# LoRaWANnode.net
KiCad netlist of a schematic drawn in EAGLE
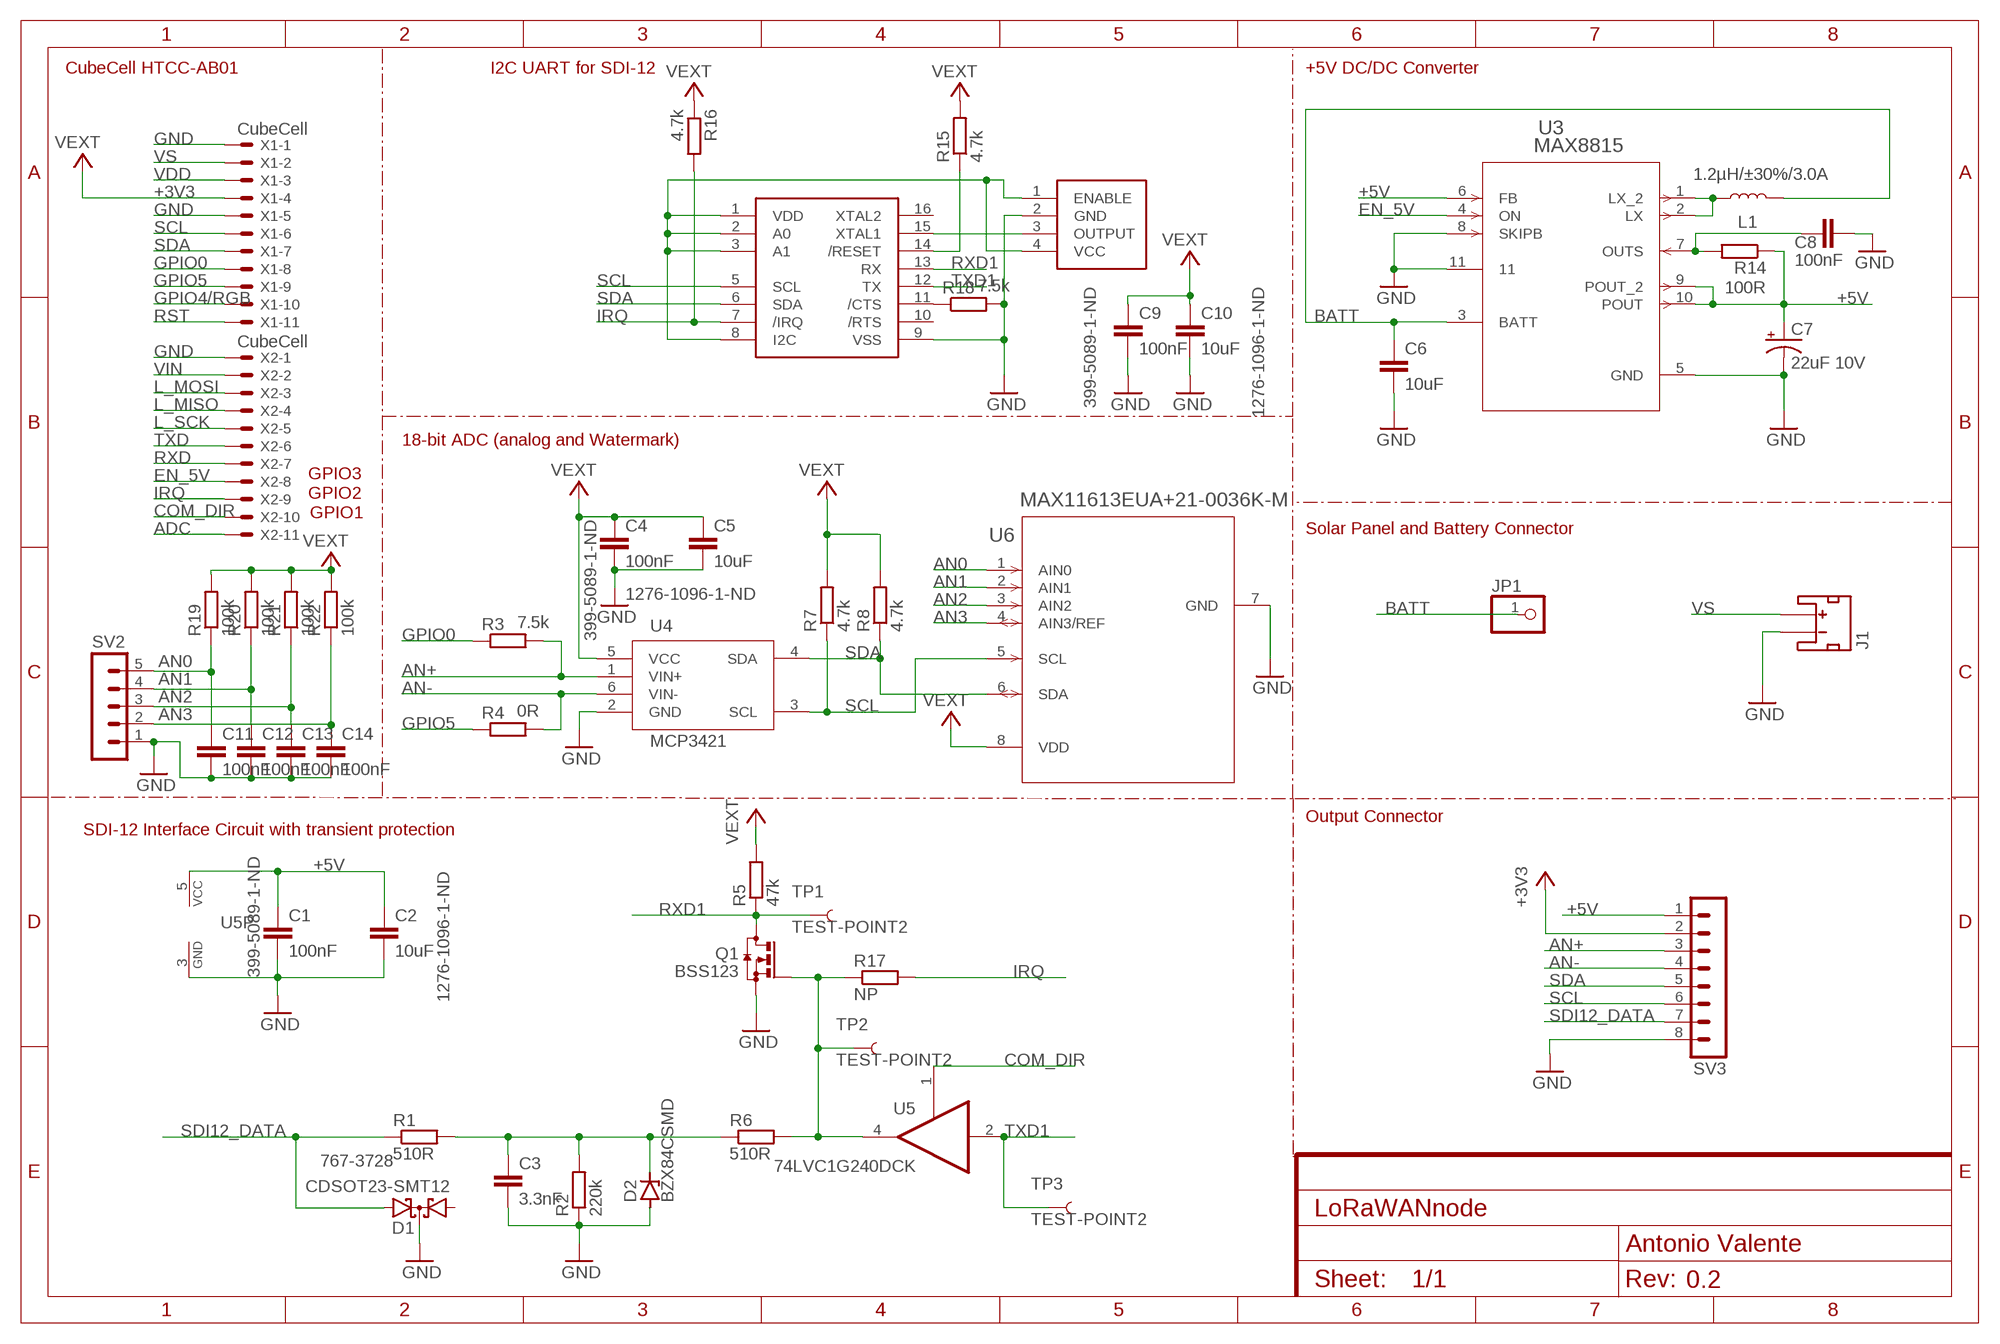
[diagram p0: schematic, sheet 1]

(export (version "E")
  (design (tool "Eeschema 10.0.6"))
  (components
    (comp (ref "C1")
      (value "100nF")
      (footprint "eagle-import:SCHMALZHAUS_0603-CAP")
      (fields
        (field (name "MF") "AVX")
        (field (name "MPN") "06033C104KAT4A")
        (field (name "OC_DIGIKEY") "399-5089-1-ND")
      )
      (libsource (lib "eagle-import") (part "SCHMALZHAUS_CAP0603-CAP"))
    )
    (comp (ref "C2")
      (value "10uF")
      (footprint "eagle-import:SCHMALZHAUS_0603-CAP")
      (fields
        (field (name "MF") "AVX")
        (field (name "MPN") "0805ZC106KAT2A")
        (field (name "OC_DIGIKEY") "1276-1096-1-ND")
      )
      (libsource (lib "eagle-import") (part "SCHMALZHAUS_CAP0603-CAP"))
    )
    (comp (ref "C3")
      (value "3.3nF")
      (footprint "eagle-import:C0603K")
      (libsource (lib "eagle-import") (part "C-EUC0603K"))
    )
    (comp (ref "C4")
      (value "100nF")
      (footprint "eagle-import:SCHMALZHAUS_0603-CAP")
      (fields
        (field (name "MF") "AVX")
        (field (name "MPN") "06033C104KAT4A")
        (field (name "OC_DIGIKEY") "399-5089-1-ND")
      )
      (libsource (lib "eagle-import") (part "SCHMALZHAUS_CAP0603-CAP"))
    )
    (comp (ref "C5")
      (value "10uF")
      (footprint "eagle-import:SCHMALZHAUS_0603-CAP")
      (fields
        (field (name "MF") "AVX")
        (field (name "MPN") "0805ZC106KAT2A")
        (field (name "OC_DIGIKEY") "1276-1096-1-ND")
      )
      (libsource (lib "eagle-import") (part "SCHMALZHAUS_CAP0603-CAP"))
    )
    (comp (ref "C6")
      (value "10uF")
      (footprint "eagle-import:0805")
      (libsource (lib "eagle-import") (part "10UF-0805-10V-10%"))
    )
    (comp (ref "C7")
      (value "22uF 10V")
      (footprint "eagle-import:EIA3216")
      (libsource (lib "eagle-import") (part "10UF-POLAR-EIA3216-16V-10%(TANT)"))
    )
    (comp (ref "C8")
      (value "100nF")
      (footprint "eagle-import:C0603K")
      (libsource (lib "eagle-import") (part "C-EUC0603K"))
    )
    (comp (ref "C9")
      (value "100nF")
      (footprint "eagle-import:SCHMALZHAUS_0603-CAP")
      (fields
        (field (name "MF") "AVX")
        (field (name "MPN") "06033C104KAT4A")
        (field (name "OC_DIGIKEY") "399-5089-1-ND")
      )
      (libsource (lib "eagle-import") (part "SCHMALZHAUS_CAP0603-CAP"))
    )
    (comp (ref "C10")
      (value "10uF")
      (footprint "eagle-import:SCHMALZHAUS_0603-CAP")
      (fields
        (field (name "MF") "AVX")
        (field (name "MPN") "0805ZC106KAT2A")
        (field (name "OC_DIGIKEY") "1276-1096-1-ND")
      )
      (libsource (lib "eagle-import") (part "SCHMALZHAUS_CAP0603-CAP"))
    )
    (comp (ref "C11")
      (value "100nF")
      (footprint "eagle-import:SCHMALZHAUS_0603-CAP")
      (fields
        (field (name "MF") "AVX")
        (field (name "MPN") "06033C104KAT4A")
        (field (name "OC_DIGIKEY") "399-5089-1-ND")
      )
      (libsource (lib "eagle-import") (part "SCHMALZHAUS_CAP0603-CAP"))
    )
    (comp (ref "C12")
      (value "100nF")
      (footprint "eagle-import:SCHMALZHAUS_0603-CAP")
      (fields
        (field (name "MF") "AVX")
        (field (name "MPN") "06033C104KAT4A")
        (field (name "OC_DIGIKEY") "399-5089-1-ND")
      )
      (libsource (lib "eagle-import") (part "SCHMALZHAUS_CAP0603-CAP"))
    )
    (comp (ref "C13")
      (value "100nF")
      (footprint "eagle-import:SCHMALZHAUS_0603-CAP")
      (fields
        (field (name "MF") "AVX")
        (field (name "MPN") "06033C104KAT4A")
        (field (name "OC_DIGIKEY") "399-5089-1-ND")
      )
      (libsource (lib "eagle-import") (part "SCHMALZHAUS_CAP0603-CAP"))
    )
    (comp (ref "C14")
      (value "100nF")
      (footprint "eagle-import:SCHMALZHAUS_0603-CAP")
      (fields
        (field (name "MF") "AVX")
        (field (name "MPN") "06033C104KAT4A")
        (field (name "OC_DIGIKEY") "399-5089-1-ND")
      )
      (libsource (lib "eagle-import") (part "SCHMALZHAUS_CAP0603-CAP"))
    )
    (comp (ref "D1")
      (value "CDSOT23-SMT12")
      (footprint "eagle-import:SOT23")
      (fields (field (name "RS") "767-3728"))
      (libsource (lib "eagle-import") (part "BAS40-05"))
    )
    (comp (ref "D2")
      (value "BZX84CSMD")
      (footprint "eagle-import:TO236")
      (libsource (lib "eagle-import") (part "BZX84CSMD"))
    )
    (comp (ref "J1")
      (value "JST_2MM_MALE")
      (footprint "eagle-import:JST-2-SMD")
      (libsource (lib "eagle-import") (part "JST_2MM_MALE"))
    )
    (comp (ref "JP1")
      (value "PINHD-1X1CB")
      (footprint "eagle-import:1X01-CLEANBIG")
      (libsource (lib "eagle-import") (part "PINHD-1X1CB"))
    )
    (comp (ref "L1")
      (value "1.2µH/±30%/3.0A")
      (footprint "eagle-import:CR54")
      (libsource (lib "eagle-import") (part "INDUCTOR-CR54-3.3UH"))
    )
    (comp (ref "Q1")
      (value "BSS123")
      (footprint "eagle-import:SOT23")
      (libsource (lib "eagle-import") (part "BSS123"))
    )
    (comp (ref "R1")
      (value "510R")
      (footprint "eagle-import:R0603")
      (libsource (lib "eagle-import") (part "resistor_348_R-EU_R0603"))
    )
    (comp (ref "R2")
      (value "220k")
      (footprint "eagle-import:R0603")
      (libsource (lib "eagle-import") (part "resistor_348_R-EU_R0603"))
    )
    (comp (ref "R3")
      (value "7.5k")
      (footprint "eagle-import:R0603")
      (libsource (lib "eagle-import") (part "resistor_348_R-EU_R0603"))
    )
    (comp (ref "R4")
      (value "0R")
      (footprint "eagle-import:R0603")
      (libsource (lib "eagle-import") (part "resistor_348_R-EU_R0603"))
    )
    (comp (ref "R5")
      (value "47k")
      (footprint "eagle-import:R0603")
      (libsource (lib "eagle-import") (part "resistor_348_R-EU_R0603"))
    )
    (comp (ref "R6")
      (value "510R")
      (footprint "eagle-import:R0603")
      (libsource (lib "eagle-import") (part "resistor_348_R-EU_R0603"))
    )
    (comp (ref "R7")
      (value "4.7k")
      (footprint "eagle-import:R0603")
      (libsource (lib "eagle-import") (part "R-EU_R0603"))
    )
    (comp (ref "R8")
      (value "4.7k")
      (footprint "eagle-import:R0603")
      (libsource (lib "eagle-import") (part "R-EU_R0603"))
    )
    (comp (ref "R14")
      (value "100R")
      (footprint "eagle-import:R0603")
      (libsource (lib "eagle-import") (part "resistor_348_R-EU_R0603"))
    )
    (comp (ref "R15")
      (value "4.7k")
      (footprint "eagle-import:R0603")
      (libsource (lib "eagle-import") (part "R-EU_R0603"))
    )
    (comp (ref "R16")
      (value "4.7k")
      (footprint "eagle-import:R0603")
      (libsource (lib "eagle-import") (part "R-EU_R0603"))
    )
    (comp (ref "R17")
      (value "NP")
      (footprint "eagle-import:R0603")
      (libsource (lib "eagle-import") (part "resistor_348_R-EU_R0603"))
    )
    (comp (ref "R18")
      (value "7.5k")
      (footprint "eagle-import:R0603")
      (libsource (lib "eagle-import") (part "resistor_348_R-EU_R0603"))
    )
    (comp (ref "R19")
      (value "100k")
      (footprint "eagle-import:R0603")
      (libsource (lib "eagle-import") (part "R-EU_R0603"))
    )
    (comp (ref "R20")
      (value "100k")
      (footprint "eagle-import:R0603")
      (libsource (lib "eagle-import") (part "R-EU_R0603"))
    )
    (comp (ref "R21")
      (value "100k")
      (footprint "eagle-import:R0603")
      (libsource (lib "eagle-import") (part "R-EU_R0603"))
    )
    (comp (ref "R22")
      (value "100k")
      (footprint "eagle-import:R0603")
      (libsource (lib "eagle-import") (part "R-EU_R0603"))
    )
    (comp (ref "SV2")
      (value "MA05-1")
      (footprint "eagle-import:MA05-1")
      (libsource (lib "eagle-import") (part "MA05-1"))
    )
    (comp (ref "SV3")
      (value "MA08-1")
      (footprint "eagle-import:MA08-1")
      (libsource (lib "eagle-import") (part "MA08-1"))
    )
    (comp (ref "TP1")
      (value "TEST-POINT2")
      (footprint "eagle-import:PAD.02X.02")
      (libsource (lib "eagle-import") (part "TEST-POINT2"))
    )
    (comp (ref "TP2")
      (value "TEST-POINT2")
      (footprint "eagle-import:PAD.02X.02")
      (libsource (lib "eagle-import") (part "TEST-POINT2"))
    )
    (comp (ref "TP3")
      (value "TEST-POINT2")
      (footprint "eagle-import:PAD.02X.02")
      (libsource (lib "eagle-import") (part "TEST-POINT2"))
    )
    (comp (ref "U1")
      (value "RICKK2_SC16IS740")
      (footprint "eagle-import:RICKK2_SC16IS740")
      (libsource (lib "eagle-import") (part "RICKK2_SC16IS740"))
    )
    (comp (ref "U2")
      (value "RICKK2_OSC-KC3225K")
      (footprint "eagle-import:RICKK2_OSC-KC3225K")
      (libsource (lib "eagle-import") (part "RICKK2_OSC-KC3225K"))
    )
    (comp (ref "U3")
      (value "MAX8815")
      (footprint "eagle-import:21-0137I_T1033-1-M")
      (fields (field (name "MANUFACTURER_PART_NUMBER") "max8815aetb+"))
      (libsource (lib "eagle-import") (part "MAX8815AETB+21-0137I_T1033-1-M"))
    )
    (comp (ref "U4")
      (value "MCP3421")
      (footprint "eagle-import:SOT23-6")
      (fields (field (name "MF") "MICROCHIP") (field (name "MPN") "MCP3421A0T-E/CH"))
      (libsource (lib "eagle-import") (part "MCP3421"))
    )
    (comp (ref "U5")
      (value "74LVC1G240DCK")
      (footprint "eagle-import:SC70-5")
      (libsource (lib "eagle-import") (part "741G126DCKLVC"))
    )
    (comp (ref "U6")
      (value "MAX11613EUA+21-0036K-M")
      (footprint "eagle-import:21-0036K-M")
      (fields (field (name "MANUFACTURER_PART_NUMBER") "max11613eua+"))
      (libsource (lib "eagle-import") (part "MAX11613EUA+21-0036K-M"))
    )
    (comp (ref "X1")
      (value "CubeCell")
      (footprint "eagle-import:22-23-2111")
      (fields (field (name "MF") "MOLEX") (field (name "MPN") "22-23-2111"))
      (libsource (lib "eagle-import") (part "22-23-2111"))
    )
    (comp (ref "X2")
      (value "CubeCell")
      (footprint "eagle-import:22-23-2111")
      (fields (field (name "MF") "MOLEX") (field (name "MPN") "22-23-2111"))
      (libsource (lib "eagle-import") (part "22-23-2111"))
    )
  )
  (nets
    (net (code "1") (name "+3V3") (class "Default")
      (node (ref "C10") (pin "1") (pinfunction "1_1") (pintype "passive"))
      (node (ref "C4") (pin "1") (pinfunction "1_1") (pintype "passive"))
      (node (ref "C5") (pin "1") (pinfunction "1_1") (pintype "passive"))
      (node (ref "C9") (pin "1") (pinfunction "1_1") (pintype "passive"))
      (node (ref "R15") (pin "2") (pinfunction "2_2") (pintype "passive"))
      (node (ref "R16") (pin "1") (pinfunction "1_1") (pintype "passive"))
      (node (ref "R19") (pin "2") (pinfunction "2_2") (pintype "passive"))
      (node (ref "R20") (pin "2") (pinfunction "2_2") (pintype "passive"))
      (node (ref "R21") (pin "2") (pinfunction "2_2") (pintype "passive"))
      (node (ref "R22") (pin "2") (pinfunction "2_2") (pintype "passive"))
      (node (ref "R5") (pin "2") (pinfunction "2_2") (pintype "passive"))
      (node (ref "R7") (pin "2") (pinfunction "2_2") (pintype "passive"))
      (node (ref "R8") (pin "2") (pinfunction "2_2") (pintype "passive"))
      (node (ref "SV3") (pin "2") (pinfunction "2_2") (pintype "passive"))
      (node (ref "U1") (pin "1") (pinfunction "VDD_1") (pintype "power_in"))
      (node (ref "U1") (pin "2") (pinfunction "A0_2") (pintype "input"))
      (node (ref "U1") (pin "3") (pinfunction "A1_3") (pintype "input"))
      (node (ref "U1") (pin "8") (pinfunction "I2C_8") (pintype "input"))
      (node (ref "U2") (pin "1") (pinfunction "ENABLE_1") (pintype "input"))
      (node (ref "U2") (pin "4") (pinfunction "VCC_4") (pintype "power_in"))
      (node (ref "U4") (pin "5") (pinfunction "VCC_5") (pintype "passive"))
      (node (ref "U6") (pin "8") (pinfunction "VDD_8") (pintype "power_in"))
      (node (ref "X1") (pin "4") (pinfunction "S_4") (pintype "passive"))
    )
    (net (code "2") (name "/+5V") (class "Default")
      (node (ref "C1") (pin "1") (pinfunction "1_1") (pintype "passive"))
      (node (ref "C2") (pin "1") (pinfunction "1_1") (pintype "passive"))
      (node (ref "C7") (pin "+") (pinfunction "+_+") (pintype "passive"))
      (node (ref "R14") (pin "1") (pinfunction "1_1") (pintype "passive"))
      (node (ref "SV3") (pin "1") (pinfunction "1_1") (pintype "passive"))
      (node (ref "U3") (pin "10") (pinfunction "POUT_10") (pintype "output"))
      (node (ref "U3") (pin "6") (pinfunction "FB_6") (pintype "input"))
      (node (ref "U3") (pin "9") (pinfunction "POUT_2_9") (pintype "output"))
      (node (ref "U5") (pin "5") (pinfunction "VCC_5") (pintype "power_in"))
    )
    (net (code "3") (name "/ADC") (class "Default")
      (node (ref "X2") (pin "11") (pinfunction "S_11") (pintype "passive"))
    )
    (net (code "4") (name "/AN+") (class "Default")
      (node (ref "R3") (pin "2") (pinfunction "2_2") (pintype "passive"))
      (node (ref "SV3") (pin "3") (pinfunction "3_3") (pintype "passive"))
      (node (ref "U4") (pin "1") (pinfunction "VIN+_1") (pintype "passive"))
    )
    (net (code "5") (name "/AN-") (class "Default")
      (node (ref "R4") (pin "2") (pinfunction "2_2") (pintype "passive"))
      (node (ref "SV3") (pin "4") (pinfunction "4_4") (pintype "passive"))
      (node (ref "U4") (pin "6") (pinfunction "VIN-_6") (pintype "passive"))
    )
    (net (code "6") (name "/AN0") (class "Default")
      (node (ref "C11") (pin "1") (pinfunction "1_1") (pintype "passive"))
      (node (ref "R19") (pin "1") (pinfunction "1_1") (pintype "passive"))
      (node (ref "SV2") (pin "5") (pinfunction "5_5") (pintype "passive"))
      (node (ref "U6") (pin "1") (pinfunction "AIN0_1") (pintype "input"))
    )
    (net (code "7") (name "/AN1") (class "Default")
      (node (ref "C12") (pin "1") (pinfunction "1_1") (pintype "passive"))
      (node (ref "R20") (pin "1") (pinfunction "1_1") (pintype "passive"))
      (node (ref "SV2") (pin "4") (pinfunction "4_4") (pintype "passive"))
      (node (ref "U6") (pin "2") (pinfunction "AIN1_2") (pintype "input"))
    )
    (net (code "8") (name "/AN2") (class "Default")
      (node (ref "C13") (pin "1") (pinfunction "1_1") (pintype "passive"))
      (node (ref "R21") (pin "1") (pinfunction "1_1") (pintype "passive"))
      (node (ref "SV2") (pin "3") (pinfunction "3_3") (pintype "passive"))
      (node (ref "U6") (pin "3") (pinfunction "AIN2_3") (pintype "input"))
    )
    (net (code "9") (name "/AN3") (class "Default")
      (node (ref "C14") (pin "1") (pinfunction "1_1") (pintype "passive"))
      (node (ref "R22") (pin "1") (pinfunction "1_1") (pintype "passive"))
      (node (ref "SV2") (pin "2") (pinfunction "2_2") (pintype "passive"))
      (node (ref "U6") (pin "4") (pinfunction "AIN3/REF_4") (pintype "bidirectional"))
    )
    (net (code "10") (name "/BATT") (class "Default")
      (node (ref "C6") (pin "1") (pinfunction "1_1") (pintype "passive"))
      (node (ref "JP1") (pin "1") (pinfunction "1_1") (pintype "passive"))
      (node (ref "L1") (pin "P$2") (pinfunction "2_P$2") (pintype "passive"))
      (node (ref "U3") (pin "3") (pinfunction "BATT_3") (pintype "power_in"))
    )
    (net (code "11") (name "/COM_DIR") (class "Default")
      (node (ref "U5") (pin "1") (pinfunction "OE_1") (pintype "input"))
      (node (ref "X2") (pin "10") (pinfunction "S_10") (pintype "passive"))
    )
    (net (code "12") (name "/EN_5V") (class "Default")
      (node (ref "U3") (pin "4") (pinfunction "ON_4") (pintype "input"))
      (node (ref "X2") (pin "8") (pinfunction "S_8") (pintype "passive"))
    )
    (net (code "13") (name "/GPIO0") (class "Default")
      (node (ref "R3") (pin "1") (pinfunction "1_1") (pintype "passive"))
      (node (ref "X1") (pin "8") (pinfunction "S_8") (pintype "passive"))
    )
    (net (code "14") (name "/GPIO4{slash}RGB") (class "Default")
      (node (ref "X1") (pin "10") (pinfunction "S_10") (pintype "passive"))
    )
    (net (code "15") (name "/GPIO5") (class "Default")
      (node (ref "R4") (pin "1") (pinfunction "1_1") (pintype "passive"))
      (node (ref "X1") (pin "9") (pinfunction "S_9") (pintype "passive"))
    )
    (net (code "16") (name "/IRQ") (class "Default")
      (node (ref "R16") (pin "2") (pinfunction "2_2") (pintype "passive"))
      (node (ref "R17") (pin "2") (pinfunction "2_2") (pintype "passive"))
      (node (ref "U1") (pin "7") (pinfunction "/IRQ_7") (pintype "output"))
      (node (ref "X2") (pin "9") (pinfunction "S_9") (pintype "passive"))
    )
    (net (code "17") (name "/L_MISO") (class "Default")
      (node (ref "X2") (pin "4") (pinfunction "S_4") (pintype "passive"))
    )
    (net (code "18") (name "/L_MOSI") (class "Default")
      (node (ref "X2") (pin "3") (pinfunction "S_3") (pintype "passive"))
    )
    (net (code "19") (name "/L_SCK") (class "Default")
      (node (ref "X2") (pin "5") (pinfunction "S_5") (pintype "passive"))
    )
    (net (code "20") (name "/RST") (class "Default")
      (node (ref "X1") (pin "11") (pinfunction "S_11") (pintype "passive"))
    )
    (net (code "21") (name "/RXD") (class "Default")
      (node (ref "X2") (pin "7") (pinfunction "S_7") (pintype "passive"))
    )
    (net (code "22") (name "/RXD1") (class "Default")
      (node (ref "Q1") (pin "3") (pinfunction "D_3") (pintype "passive"))
      (node (ref "R5") (pin "1") (pinfunction "1_1") (pintype "passive"))
      (node (ref "TP1") (pin "P$1") (pinfunction "1_P$1") (pintype "bidirectional"))
      (node (ref "U1") (pin "13") (pinfunction "RX_13") (pintype "input"))
    )
    (net (code "23") (name "/SCL") (class "Default")
      (node (ref "R7") (pin "1") (pinfunction "1_1") (pintype "passive"))
      (node (ref "SV3") (pin "6") (pinfunction "6_6") (pintype "passive"))
      (node (ref "U1") (pin "5") (pinfunction "SCL_5") (pintype "bidirectional"))
      (node (ref "U4") (pin "3") (pinfunction "SCL_3") (pintype "passive"))
      (node (ref "U6") (pin "5") (pinfunction "SCL_5") (pintype "input"))
      (node (ref "X1") (pin "6") (pinfunction "S_6") (pintype "passive"))
    )
    (net (code "24") (name "/SDA") (class "Default")
      (node (ref "R8") (pin "1") (pinfunction "1_1") (pintype "passive"))
      (node (ref "SV3") (pin "5") (pinfunction "5_5") (pintype "passive"))
      (node (ref "U1") (pin "6") (pinfunction "SDA_6") (pintype "bidirectional"))
      (node (ref "U4") (pin "4") (pinfunction "SDA_4") (pintype "passive"))
      (node (ref "U6") (pin "6") (pinfunction "SDA_6") (pintype "bidirectional"))
      (node (ref "X1") (pin "7") (pinfunction "S_7") (pintype "passive"))
    )
    (net (code "25") (name "/SDI12_DATA") (class "Default")
      (node (ref "D1") (pin "2") (pinfunction "A2_2") (pintype "passive"))
      (node (ref "R1") (pin "1") (pinfunction "1_1") (pintype "passive"))
      (node (ref "SV3") (pin "7") (pinfunction "7_7") (pintype "passive"))
    )
    (net (code "26") (name "/TXD") (class "Default")
      (node (ref "X2") (pin "6") (pinfunction "S_6") (pintype "passive"))
    )
    (net (code "27") (name "/TXD1") (class "Default")
      (node (ref "TP3") (pin "P$1") (pinfunction "1_P$1") (pintype "bidirectional"))
      (node (ref "U1") (pin "12") (pinfunction "TX_12") (pintype "output"))
      (node (ref "U5") (pin "2") (pinfunction "I_2") (pintype "input"))
    )
    (net (code "28") (name "/VDD") (class "Default")
      (node (ref "X1") (pin "3") (pinfunction "S_3") (pintype "passive"))
    )
    (net (code "29") (name "/VIN") (class "Default")
      (node (ref "X2") (pin "2") (pinfunction "S_2") (pintype "passive"))
    )
    (net (code "30") (name "/VS") (class "Default")
      (node (ref "J1") (pin "2") (pinfunction "+_2") (pintype "bidirectional"))
      (node (ref "X1") (pin "2") (pinfunction "S_2") (pintype "passive"))
    )
    (net (code "31") (name "GND") (class "Default")
      (node (ref "C1") (pin "2") (pinfunction "2_2") (pintype "passive"))
      (node (ref "C10") (pin "2") (pinfunction "2_2") (pintype "passive"))
      (node (ref "C11") (pin "2") (pinfunction "2_2") (pintype "passive"))
      (node (ref "C12") (pin "2") (pinfunction "2_2") (pintype "passive"))
      (node (ref "C13") (pin "2") (pinfunction "2_2") (pintype "passive"))
      (node (ref "C14") (pin "2") (pinfunction "2_2") (pintype "passive"))
      (node (ref "C2") (pin "2") (pinfunction "2_2") (pintype "passive"))
      (node (ref "C3") (pin "2") (pinfunction "2_2") (pintype "passive"))
      (node (ref "C4") (pin "2") (pinfunction "2_2") (pintype "passive"))
      (node (ref "C5") (pin "2") (pinfunction "2_2") (pintype "passive"))
      (node (ref "C6") (pin "2") (pinfunction "2_2") (pintype "passive"))
      (node (ref "C7") (pin "-") (pinfunction "-_-") (pintype "passive"))
      (node (ref "C8") (pin "2") (pinfunction "2_2") (pintype "passive"))
      (node (ref "C9") (pin "2") (pinfunction "2_2") (pintype "passive"))
      (node (ref "D1") (pin "3") (pinfunction "C_3") (pintype "passive"))
      (node (ref "D2") (pin "A") (pinfunction "A_A") (pintype "passive"))
      (node (ref "J1") (pin "1") (pinfunction "-_1") (pintype "bidirectional"))
      (node (ref "Q1") (pin "2") (pinfunction "S_2") (pintype "passive"))
      (node (ref "R18") (pin "2") (pinfunction "2_2") (pintype "passive"))
      (node (ref "R2") (pin "1") (pinfunction "1_1") (pintype "passive"))
      (node (ref "SV2") (pin "1") (pinfunction "1_1") (pintype "passive"))
      (node (ref "SV3") (pin "8") (pinfunction "8_8") (pintype "passive"))
      (node (ref "U1") (pin "9") (pinfunction "VSS_9") (pintype "power_in"))
      (node (ref "U2") (pin "2") (pinfunction "GND_2") (pintype "power_in"))
      (node (ref "U3") (pin "11") (pinfunction "11_11") (pintype "passive"))
      (node (ref "U3") (pin "5") (pinfunction "GND_5") (pintype "power_in"))
      (node (ref "U3") (pin "8") (pinfunction "SKIPB_8") (pintype "input"))
      (node (ref "U4") (pin "2") (pinfunction "GND_2") (pintype "passive"))
      (node (ref "U5") (pin "3") (pinfunction "GND_3") (pintype "power_in"))
      (node (ref "U6") (pin "7") (pinfunction "GND_7") (pintype "power_in"))
      (node (ref "X1") (pin "1") (pinfunction "S_1") (pintype "passive"))
      (node (ref "X1") (pin "5") (pinfunction "S_5") (pintype "passive"))
      (node (ref "X2") (pin "1") (pinfunction "S_1") (pintype "passive"))
    )
    (net (code "32") (name "Net-(C3-Pad1)") (class "Default")
      (node (ref "C3") (pin "1") (pinfunction "1_1") (pintype "passive"))
      (node (ref "D2") (pin "C") (pinfunction "C_C") (pintype "passive"))
      (node (ref "R1") (pin "2") (pinfunction "2_2") (pintype "passive"))
      (node (ref "R2") (pin "2") (pinfunction "2_2") (pintype "passive"))
      (node (ref "R6") (pin "1") (pinfunction "1_1") (pintype "passive"))
    )
    (net (code "33") (name "Net-(L1-1)") (class "Default")
      (node (ref "L1") (pin "P$1") (pinfunction "1_P$1") (pintype "passive"))
      (node (ref "U3") (pin "1") (pinfunction "LX_2_1") (pintype "output"))
      (node (ref "U3") (pin "2") (pinfunction "LX_2") (pintype "output"))
    )
    (net (code "34") (name "Net-(Q1-G)") (class "Default")
      (node (ref "Q1") (pin "1") (pinfunction "G_1") (pintype "passive"))
      (node (ref "R17") (pin "1") (pinfunction "1_1") (pintype "passive"))
      (node (ref "R6") (pin "2") (pinfunction "2_2") (pintype "passive"))
      (node (ref "TP2") (pin "P$1") (pinfunction "1_P$1") (pintype "bidirectional"))
      (node (ref "U5") (pin "4") (pinfunction "O_4") (pintype "output"))
    )
    (net (code "35") (name "Net-(U1-XTAL1)") (class "Default")
      (node (ref "U1") (pin "15") (pinfunction "XTAL1_15") (pintype "input"))
      (node (ref "U2") (pin "3") (pinfunction "OUTPUT_3") (pintype "output"))
    )
    (net (code "36") (name "Net-(U1-{slash}CTS)") (class "Default")
      (node (ref "R18") (pin "1") (pinfunction "1_1") (pintype "passive"))
      (node (ref "U1") (pin "11") (pinfunction "/CTS_11") (pintype "input"))
    )
    (net (code "37") (name "Net-(U1-{slash}RESET)") (class "Default")
      (node (ref "R15") (pin "1") (pinfunction "1_1") (pintype "passive"))
      (node (ref "U1") (pin "14") (pinfunction "/RESET_14") (pintype "input"))
    )
    (net (code "38") (name "Net-(U3-OUTS)") (class "Default")
      (node (ref "C8") (pin "1") (pinfunction "1_1") (pintype "passive"))
      (node (ref "R14") (pin "2") (pinfunction "2_2") (pintype "passive"))
      (node (ref "U3") (pin "7") (pinfunction "OUTS_7") (pintype "input"))
    )
    (net (code "39") (name "unconnected-(D1-A1-Pad1)") (class "Default")
      (node (ref "D1") (pin "1") (pinfunction "A1_1") (pintype "passive"))
    )
    (net (code "40") (name "unconnected-(J1-PAD1-PadNC1)") (class "Default")
      (node (ref "J1") (pin "NC1") (pinfunction "PAD1_NC1") (pintype "bidirectional"))
    )
    (net (code "41") (name "unconnected-(J1-PAD2-PadNC2)") (class "Default")
      (node (ref "J1") (pin "NC2") (pinfunction "PAD2_NC2") (pintype "bidirectional"))
    )
    (net (code "42") (name "unconnected-(U1-XTAL2-Pad16)") (class "Default")
      (node (ref "U1") (pin "16") (pinfunction "XTAL2_16") (pintype "bidirectional"))
    )
    (net (code "43") (name "unconnected-(U1-{slash}RTS-Pad10)") (class "Default")
      (node (ref "U1") (pin "10") (pinfunction "/RTS_10") (pintype "output"))
    )
  )
)
